# 9_GPSGNSS.net
KiCad netlist of a schematic drawn in Altium Designer
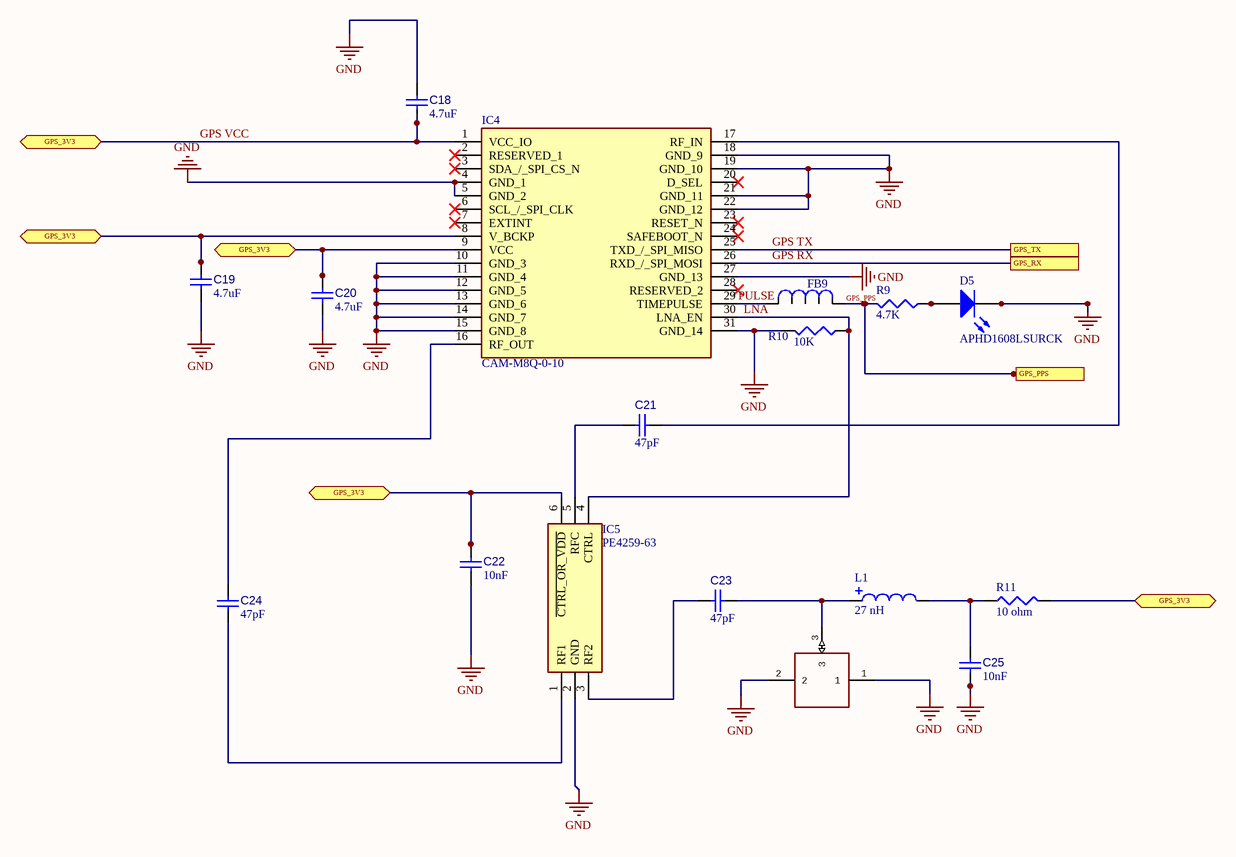
[diagram p0: [9]GPSGNSS.SchDoc]

(export (version "E")
  (design (tool "Eeschema 10.0.6"))
  (components
    (comp (ref "C18")
      (value "4.7uF")
      (footprint "CAPC1608X90X40ML10T20")
      (description "Chip Capacitor, 4.7uF, +/- 10%, 50 V, 0603 (1608 Metric)")
      (fields (field (name "TOLERANCE") "10%"))
      (libsource (lib "Latium Technologies") (part "CAP-NP-2"))
    )
    (comp (ref "C19")
      (value "4.7uF")
      (footprint "CAPC1608X90X40ML10T20")
      (description "Chip Capacitor, 4.7uF, +/- 10%, 50 V, 0603 (1608 Metric)")
      (fields (field (name "TOLERANCE") "10%"))
      (libsource (lib "Latium Technologies") (part "CAP-NP-2"))
    )
    (comp (ref "C20")
      (value "4.7uF")
      (footprint "CAPC1608X90X40ML10T20")
      (description "Chip Capacitor, 4.7uF, +/- 10%, 50 V, 0603 (1608 Metric)")
      (fields (field (name "TOLERANCE") "10%"))
      (libsource (lib "Latium Technologies") (part "CAP-NP-2"))
    )
    (comp (ref "C21")
      (value "47pF")
      (footprint "CAPC1608X90X40ML10T20")
      (description "Chip Capacitor, 47pF, +/- 10%, 50 V, 0603 (1608 Metric)")
      (fields (field (name "TOLERANCE") "10%"))
      (libsource (lib "Latium Technologies") (part "CAP-NP-2"))
    )
    (comp (ref "C22")
      (value "10nF")
      (footprint "CAPC1608X90X40ML10T20")
      (description "Chip Capacitor, 10 nF, +/- 10%, 50 V, 0603 (1608 Metric)")
      (fields (field (name "TOLERANCE") "10%"))
      (libsource (lib "Latium Technologies") (part "CAP-NP-2"))
    )
    (comp (ref "C23")
      (value "47pF")
      (footprint "CAPC1608X90X40ML10T20")
      (description "Chip Capacitor, 47pF, +/- 10%, 50 V, 0603 (1608 Metric)")
      (fields (field (name "TOLERANCE") "10%"))
      (libsource (lib "Latium Technologies") (part "CAP-NP-2"))
    )
    (comp (ref "C24")
      (value "47pF")
      (footprint "CAPC1608X90X40ML10T20")
      (description "Chip Capacitor, 47pF, +/- 10%, 50 V, 0603 (1608 Metric)")
      (fields (field (name "TOLERANCE") "10%"))
      (libsource (lib "Latium Technologies") (part "CAP-NP-2"))
    )
    (comp (ref "C25")
      (value "10nF")
      (footprint "CAPC1608X90X40ML10T20")
      (description "Chip Capacitor, 10 nF, +/- 10%, 50 V, 0603 (1608 Metric)")
      (fields (field (name "TOLERANCE") "10%"))
      (libsource (lib "Latium Technologies") (part "CAP-NP-2"))
    )
    (comp (ref "CONN2")
      (value "U.FL-R-SMT-1")
      (footprint "U.FL-R-SMT-1")
      (fields (field (name "LIBRARYNAME") "Kris"))
      (libsource (lib "Schlib_For_High_Voltage_Sensor") (part "U.FL-R-SMT-1"))
    )
    (comp (ref "D5")
      (value "APHD1608LSURCK")
      (footprint "LED BLUE CLEAR [0603] 2mA")
      (description "LED RED  [0603] 2mA")
      (fields (field (name "PN") "APHD1608LSURCK"))
      (libsource (lib "MasterLib") (part "LED BLUE CLEAR 1608 SMD"))
    )
    (comp (ref "FB9")
      (value "BLM18AG102SN1D")
      (footprint "Ferrite Bead")
      (description "Ferrite Bead 1KOhm @100MHz")
      (libsource (lib "MasterLib") (part "Ferrite Bead"))
    )
    (comp (ref "IC4")
      (value "CAM-M8Q-0-10")
      (footprint "CAM-M8Q")
      (description "Integrated Circuit")
      (libsource (lib "Schlib_For_High_Voltage_Sensor") (part "CAM-M8Q-0-10"))
    )
    (comp (ref "IC5")
      (value "PE4259-63")
      (footprint "SamacSys:SOT65P210X110-6N")
      (description "Integrated Circuit")
      (libsource (lib "*") (part "PE4259-63"))
    )
    (comp (ref "L1")
      (value "27 nH")
      (footprint "INDC1005X55X25ML5T10")
      (description "Chip Inductor, 27 nH, +/- 0.3 nH, 300 mA, -55 to 125 degC, 0402 (1005 Metric), RoHS, Tape and Reel")
      (fields (field (name "MANUFACTURER") "Murata") (field (name "TOLERANCE") "5%"))
      (libsource (lib "Latium Technologies") (part "IND_POLAR-2"))
    )
    (comp (ref "R9")
      (value "4.7K")
      (footprint "RESC0603")
      (description "RESISTOR")
      (libsource (lib "HVLib") (part "RESISTOR"))
    )
    (comp (ref "R10")
      (value "10K")
      (footprint "RESC0603")
      (description "RESISTOR")
      (libsource (lib "HVLib") (part "RESISTOR"))
    )
    (comp (ref "R11")
      (value "10 ohm")
      (footprint "RESC0603")
      (description "RESISTOR")
      (libsource (lib "HVLib") (part "RESISTOR"))
    )
  )
  (nets
    (net (code "1") (name "/GPS RX") (class "Default")
      (node (ref "IC4") (pin "26") (pinfunction "RXD_/_SPI_MOSI_26") (pintype "passive"))
    )
    (net (code "2") (name "/GPS TX") (class "Default")
      (node (ref "IC4") (pin "25") (pinfunction "TXD_/_SPI_MISO_25") (pintype "passive"))
    )
    (net (code "3") (name "/GPS VCC") (class "Default")
      (node (ref "C18") (pin "2") (pinfunction "2_2") (pintype "passive"))
      (node (ref "C19") (pin "1") (pinfunction "1_1") (pintype "passive"))
      (node (ref "C20") (pin "1") (pinfunction "1_1") (pintype "passive"))
      (node (ref "C22") (pin "2") (pinfunction "2_2") (pintype "passive"))
      (node (ref "IC4") (pin "1") (pinfunction "VCC_IO_1") (pintype "passive"))
      (node (ref "IC4") (pin "8") (pinfunction "V_BCKP_8") (pintype "passive"))
      (node (ref "IC4") (pin "9") (pinfunction "VCC_9") (pintype "passive"))
      (node (ref "IC5") (pin "6") (pinfunction "~{CTRL_OR_VDD}_6") (pintype "passive"))
      (node (ref "R11") (pin "2") (pintype "passive"))
    )
    (net (code "4") (name "/GPS_PPS") (class "Default")
      (node (ref "FB9") (pin "2") (pinfunction "2_2") (pintype "passive"))
      (node (ref "R9") (pin "2") (pintype "passive"))
    )
    (net (code "5") (name "/LNA") (class "Default")
      (node (ref "IC4") (pin "30") (pinfunction "LNA_EN_30") (pintype "passive"))
      (node (ref "IC5") (pin "4") (pinfunction "CTRL_4") (pintype "passive"))
      (node (ref "R10") (pin "1") (pintype "passive"))
    )
    (net (code "6") (name "/PULSE") (class "Default")
      (node (ref "FB9") (pin "1") (pinfunction "1_1") (pintype "passive"))
      (node (ref "IC4") (pin "29") (pinfunction "TIMEPULSE_29") (pintype "passive"))
    )
    (net (code "7") (name "GND") (class "Default")
      (node (ref "C18") (pin "1") (pinfunction "1_1") (pintype "passive"))
      (node (ref "C19") (pin "2") (pinfunction "2_2") (pintype "passive"))
      (node (ref "C20") (pin "2") (pinfunction "2_2") (pintype "passive"))
      (node (ref "C22") (pin "1") (pinfunction "1_1") (pintype "passive"))
      (node (ref "C25") (pin "1") (pinfunction "1_1") (pintype "passive"))
      (node (ref "CONN2") (pin "1") (pinfunction "1_1") (pintype "power_in"))
      (node (ref "CONN2") (pin "2") (pinfunction "2_2") (pintype "power_in"))
      (node (ref "D5") (pin "1") (pinfunction "1_1") (pintype "passive"))
      (node (ref "IC4") (pin "10") (pinfunction "GND_3_10") (pintype "passive"))
      (node (ref "IC4") (pin "11") (pinfunction "GND_4_11") (pintype "passive"))
      (node (ref "IC4") (pin "12") (pinfunction "GND_5_12") (pintype "passive"))
      (node (ref "IC4") (pin "13") (pinfunction "GND_6_13") (pintype "passive"))
      (node (ref "IC4") (pin "14") (pinfunction "GND_7_14") (pintype "passive"))
      (node (ref "IC4") (pin "15") (pinfunction "GND_8_15") (pintype "passive"))
      (node (ref "IC4") (pin "18") (pinfunction "GND_9_18") (pintype "passive"))
      (node (ref "IC4") (pin "19") (pinfunction "GND_10_19") (pintype "passive"))
      (node (ref "IC4") (pin "21") (pinfunction "GND_11_21") (pintype "passive"))
      (node (ref "IC4") (pin "22") (pinfunction "GND_12_22") (pintype "passive"))
      (node (ref "IC4") (pin "27") (pinfunction "GND_13_27") (pintype "passive"))
      (node (ref "IC4") (pin "31") (pinfunction "GND_14_31") (pintype "passive"))
      (node (ref "IC4") (pin "4") (pinfunction "GND_1_4") (pintype "passive"))
      (node (ref "IC4") (pin "5") (pinfunction "GND_2_5") (pintype "passive"))
      (node (ref "IC5") (pin "2") (pinfunction "GND_2") (pintype "passive"))
      (node (ref "R10") (pin "2") (pintype "passive"))
    )
    (net (code "8") (name "Net-(C23-Pad2)") (class "Default")
      (node (ref "C23") (pin "2") (pinfunction "2_2") (pintype "passive"))
      (node (ref "CONN2") (pin "3") (pinfunction "3_3") (pintype "bidirectional"))
      (node (ref "L1") (pin "1") (pinfunction "1_1") (pintype "passive"))
    )
    (net (code "9") (name "Net-(C25-Pad2)") (class "Default")
      (node (ref "C25") (pin "2") (pinfunction "2_2") (pintype "passive"))
      (node (ref "L1") (pin "2") (pinfunction "2_2") (pintype "passive"))
      (node (ref "R11") (pin "1") (pintype "passive"))
    )
    (net (code "10") (name "Net-(D5-Pad2)") (class "Default")
      (node (ref "D5") (pin "2") (pinfunction "2_2") (pintype "passive"))
      (node (ref "R9") (pin "1") (pintype "passive"))
    )
    (net (code "11") (name "Net-(IC4-RF_IN)") (class "Default")
      (node (ref "C21") (pin "2") (pinfunction "2_2") (pintype "passive"))
      (node (ref "IC4") (pin "17") (pinfunction "RF_IN_17") (pintype "passive"))
    )
    (net (code "12") (name "Net-(IC4-RF_OUT)") (class "Default")
      (node (ref "C24") (pin "2") (pinfunction "2_2") (pintype "passive"))
      (node (ref "IC4") (pin "16") (pinfunction "RF_OUT_16") (pintype "passive"))
    )
    (net (code "13") (name "Net-(IC5-RF1)") (class "Default")
      (node (ref "C24") (pin "1") (pinfunction "1_1") (pintype "passive"))
      (node (ref "IC5") (pin "1") (pinfunction "RF1_1") (pintype "passive"))
    )
    (net (code "14") (name "Net-(IC5-RF2)") (class "Default")
      (node (ref "C23") (pin "1") (pinfunction "1_1") (pintype "passive"))
      (node (ref "IC5") (pin "3") (pinfunction "RF2_3") (pintype "passive"))
    )
    (net (code "15") (name "Net-(IC5-RFC)") (class "Default")
      (node (ref "C21") (pin "1") (pinfunction "1_1") (pintype "passive"))
      (node (ref "IC5") (pin "5") (pinfunction "RFC_5") (pintype "passive"))
    )
    (net (code "16") (name "unconnected-(IC4-D_SEL-Pad20)") (class "Default")
      (node (ref "IC4") (pin "20") (pinfunction "D_SEL_20") (pintype "passive+no_connect"))
    )
    (net (code "17") (name "unconnected-(IC4-EXTINT-Pad7)") (class "Default")
      (node (ref "IC4") (pin "7") (pinfunction "EXTINT_7") (pintype "passive+no_connect"))
    )
    (net (code "18") (name "unconnected-(IC4-RESERVED_1-Pad2)") (class "Default")
      (node (ref "IC4") (pin "2") (pinfunction "RESERVED_1_2") (pintype "passive+no_connect"))
    )
    (net (code "19") (name "unconnected-(IC4-RESERVED_2-Pad28)") (class "Default")
      (node (ref "IC4") (pin "28") (pinfunction "RESERVED_2_28") (pintype "passive+no_connect"))
    )
    (net (code "20") (name "unconnected-(IC4-RESET_N-Pad23)") (class "Default")
      (node (ref "IC4") (pin "23") (pinfunction "RESET_N_23") (pintype "passive+no_connect"))
    )
    (net (code "21") (name "unconnected-(IC4-SAFEBOOT_N-Pad24)") (class "Default")
      (node (ref "IC4") (pin "24") (pinfunction "SAFEBOOT_N_24") (pintype "passive+no_connect"))
    )
    (net (code "22") (name "unconnected-(IC4-SCL_{slash}_SPI_CLK-Pad6)") (class "Default")
      (node (ref "IC4") (pin "6") (pinfunction "SCL_/_SPI_CLK_6") (pintype "passive+no_connect"))
    )
    (net (code "23") (name "unconnected-(IC4-SDA_{slash}_SPI_CS_N-Pad3)") (class "Default")
      (node (ref "IC4") (pin "3") (pinfunction "SDA_/_SPI_CS_N_3") (pintype "passive+no_connect"))
    )
  )
)
